# MAX30003.net
KiCad netlist of a schematic drawn in EAGLE
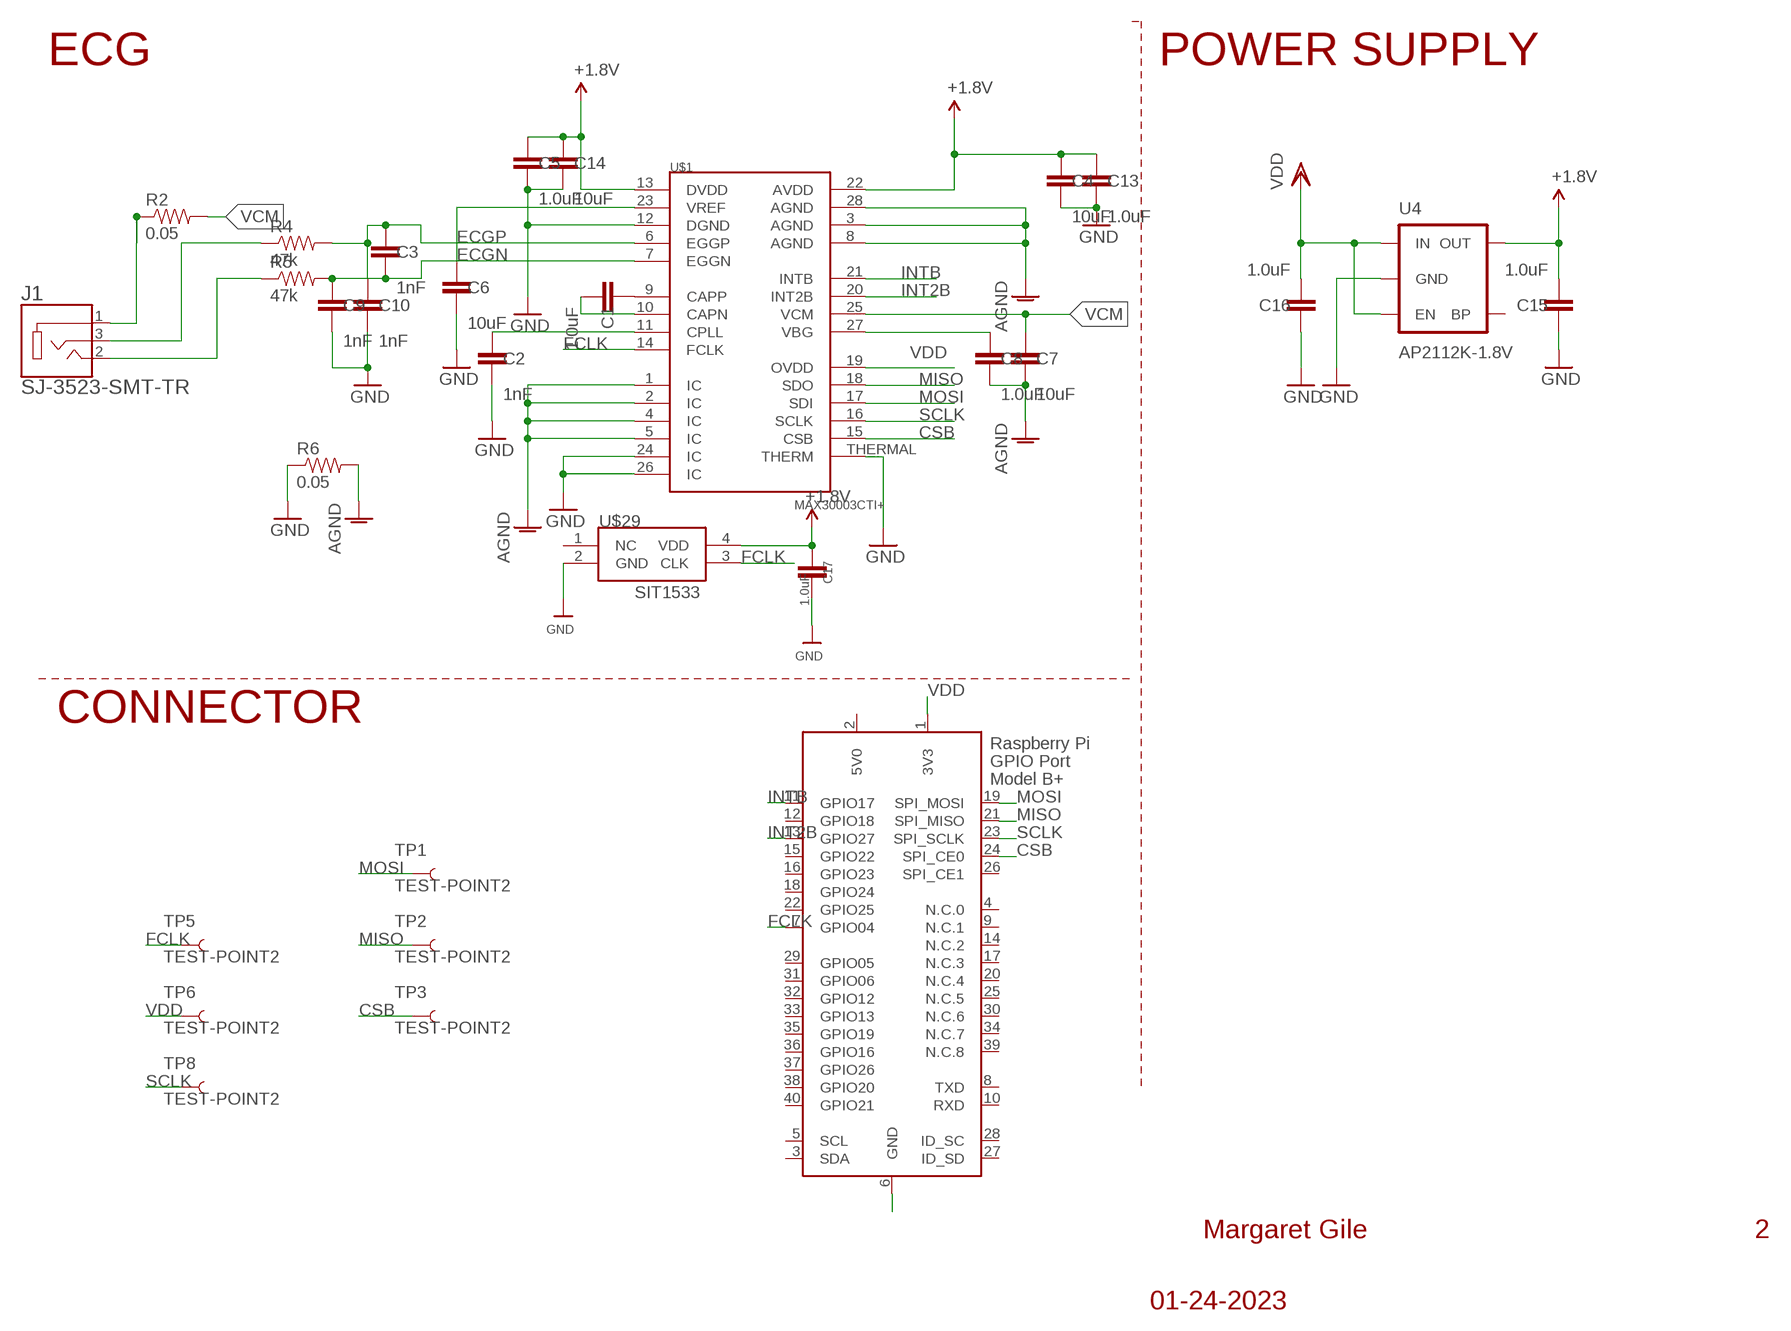
[diagram p0: schematic, sheet 1]

(export (version "E")
  (design (tool "Eeschema 10.0.6"))
  (components
    (comp (ref "C1")
      (value "1.0uF")
      (footprint "eagle-import:0603")
      (libsource (lib "eagle-import") (part "1.0UF-0603-16V-10%"))
    )
    (comp (ref "C2")
      (value "1nF")
      (footprint "eagle-import:0603")
      (libsource (lib "eagle-import") (part "1.0NF/1000PF-0603-50V-10%"))
    )
    (comp (ref "C3")
      (value "1nF")
      (footprint "eagle-import:0603")
      (libsource (lib "eagle-import") (part "1.0NF/1000PF-0603-50V-10%"))
    )
    (comp (ref "C4")
      (value "10uF")
      (footprint "eagle-import:0603")
      (libsource (lib "eagle-import") (part "10UF-0603-6.3V-20%"))
    )
    (comp (ref "C5")
      (value "1.0uF")
      (footprint "eagle-import:0603")
      (libsource (lib "eagle-import") (part "1.0UF-0603-16V-10%"))
    )
    (comp (ref "C6")
      (value "10uF")
      (footprint "eagle-import:0603")
      (libsource (lib "eagle-import") (part "10UF-0603-6.3V-20%"))
    )
    (comp (ref "C7")
      (value "10uF")
      (footprint "eagle-import:0603")
      (libsource (lib "eagle-import") (part "10UF-0603-6.3V-20%"))
    )
    (comp (ref "C8")
      (value "1.0uF")
      (footprint "eagle-import:0603")
      (libsource (lib "eagle-import") (part "1.0UF-0603-16V-10%"))
    )
    (comp (ref "C9")
      (value "1nF")
      (footprint "eagle-import:0603")
      (libsource (lib "eagle-import") (part "1.0NF/1000PF-0603-50V-10%"))
    )
    (comp (ref "C10")
      (value "1nF")
      (footprint "eagle-import:0603")
      (libsource (lib "eagle-import") (part "1.0NF/1000PF-0603-50V-10%"))
    )
    (comp (ref "C13")
      (value "1.0uF")
      (footprint "eagle-import:0603")
      (libsource (lib "eagle-import") (part "1.0UF-0603-16V-10%"))
    )
    (comp (ref "C14")
      (value "10uF")
      (footprint "eagle-import:0603")
      (libsource (lib "eagle-import") (part "10UF-0603-6.3V-20%"))
    )
    (comp (ref "C15")
      (value "1.0uF")
      (footprint "eagle-import:0603")
      (libsource (lib "eagle-import") (part "1.0UF-0603-16V-10%"))
    )
    (comp (ref "C16")
      (value "1.0uF")
      (footprint "eagle-import:0603")
      (libsource (lib "eagle-import") (part "1.0UF-0603-16V-10%"))
    )
    (comp (ref "C17")
      (value "1.0uF")
      (footprint "eagle-import:0603")
      (libsource (lib "eagle-import") (part "1.0UF-0603-16V-10%"))
    )
    (comp (ref "J1")
      (value "SJ-3523-SMT-TR")
      (footprint "eagle-import:CUI_SJ-3523-SMT-TR")
      (fields (field (name "MF") "CUI Devices"))
      (libsource (lib "eagle-import") (part "SJ-3523-SMT-TR"))
    )
    (comp (ref "R2")
      (value "0.05")
      (footprint "eagle-import:0603")
      (libsource (lib "eagle-import") (part "0.05OHM-0603-1/5W-1%"))
    )
    (comp (ref "R4")
      (value "47k")
      (footprint "eagle-import:0603")
      (libsource (lib "eagle-import") (part "47KOHM-0603-1/10W-1%"))
    )
    (comp (ref "R5")
      (value "47k")
      (footprint "eagle-import:0603")
      (libsource (lib "eagle-import") (part "47KOHM-0603-1/10W-1%"))
    )
    (comp (ref "R6")
      (value "0.05")
      (footprint "eagle-import:0603")
      (libsource (lib "eagle-import") (part "0.05OHM-0603-1/5W-1%"))
    )
    (comp (ref "TP1")
      (value "TEST-POINT2")
      (footprint "eagle-import:PAD.02X.02")
      (libsource (lib "eagle-import") (part "TEST-POINT2"))
    )
    (comp (ref "TP2")
      (value "TEST-POINT2")
      (footprint "eagle-import:PAD.02X.02")
      (libsource (lib "eagle-import") (part "TEST-POINT2"))
    )
    (comp (ref "TP3")
      (value "TEST-POINT2")
      (footprint "eagle-import:PAD.02X.02")
      (libsource (lib "eagle-import") (part "TEST-POINT2"))
    )
    (comp (ref "TP5")
      (value "TEST-POINT2")
      (footprint "eagle-import:PAD.02X.02")
      (libsource (lib "eagle-import") (part "TEST-POINT2"))
    )
    (comp (ref "TP6")
      (value "TEST-POINT2")
      (footprint "eagle-import:PAD.02X.02")
      (libsource (lib "eagle-import") (part "TEST-POINT2"))
    )
    (comp (ref "TP8")
      (value "TEST-POINT2")
      (footprint "eagle-import:PAD.02X.02")
      (libsource (lib "eagle-import") (part "TEST-POINT2"))
    )
    (comp (ref "U$1")
      (value "MAX30003CTI+")
      (footprint "eagle-import:QFN-28")
      (libsource (lib "eagle-import") (part "MAX30003"))
    )
    (comp (ref "U$29")
      (value "SIT1533")
      (footprint "eagle-import:SIT1533")
      (libsource (lib "eagle-import") (part "SIT1533"))
    )
    (comp (ref "U4")
      (value "AP2112K-1.8V")
      (footprint "eagle-import:SOT23-5")
      (libsource (lib "eagle-import") (part "V_REG_LDOSMD"))
    )
    (comp (ref "X1")
      (value "RASPI_BOARD_B+_HDC")
      (footprint "eagle-import:RASPI_BOARD_B+HAT_DF_CF")
      (libsource (lib "eagle-import") (part "RASPI_BOARD_B+_HDC"))
    )
  )
  (nets
    (net (code "1") (name "+1.8V") (class "Default")
      (node (ref "C13") (pin "1") (pinfunction "1_1") (pintype "passive"))
      (node (ref "C14") (pin "1") (pinfunction "1_1") (pintype "passive"))
      (node (ref "C15") (pin "2") (pinfunction "2_2") (pintype "passive"))
      (node (ref "C17") (pin "1") (pinfunction "1_1") (pintype "passive"))
      (node (ref "C4") (pin "1") (pinfunction "1_1") (pintype "passive"))
      (node (ref "C5") (pin "1") (pinfunction "1_1") (pintype "passive"))
      (node (ref "U$1") (pin "13") (pinfunction "DVDD_13") (pintype "bidirectional"))
      (node (ref "U$1") (pin "22") (pinfunction "AVDD_22") (pintype "bidirectional"))
      (node (ref "U$29") (pin "4") (pinfunction "VDD_4") (pintype "bidirectional"))
      (node (ref "U4") (pin "5") (pinfunction "OUT_5") (pintype "passive"))
    )
    (net (code "2") (name "/5V0") (class "Default")
      (node (ref "X1") (pin "2") (pinfunction "5V0_2") (pintype "power_in"))
    )
    (net (code "3") (name "/CSB") (class "Default")
      (node (ref "TP3") (pin "P$1") (pinfunction "1_P$1") (pintype "bidirectional"))
      (node (ref "U$1") (pin "15") (pinfunction "CSB_15") (pintype "bidirectional"))
      (node (ref "X1") (pin "24") (pinfunction "SPI_CE0_24") (pintype "bidirectional"))
    )
    (net (code "4") (name "/ECGN") (class "Default")
      (node (ref "C3") (pin "2") (pinfunction "2_2") (pintype "passive"))
      (node (ref "C9") (pin "1") (pinfunction "1_1") (pintype "passive"))
      (node (ref "R5") (pin "2") (pinfunction "2_2") (pintype "passive"))
      (node (ref "U$1") (pin "7") (pinfunction "EGGN_7") (pintype "bidirectional"))
    )
    (net (code "5") (name "/ECGP") (class "Default")
      (node (ref "C10") (pin "1") (pinfunction "1_1") (pintype "passive"))
      (node (ref "C3") (pin "1") (pinfunction "1_1") (pintype "passive"))
      (node (ref "R4") (pin "2") (pinfunction "2_2") (pintype "passive"))
      (node (ref "U$1") (pin "6") (pinfunction "EGGP_6") (pintype "bidirectional"))
    )
    (net (code "6") (name "/FCLK") (class "Default")
      (node (ref "TP5") (pin "P$1") (pinfunction "1_P$1") (pintype "bidirectional"))
      (node (ref "U$1") (pin "14") (pinfunction "FCLK_14") (pintype "bidirectional"))
      (node (ref "U$29") (pin "3") (pinfunction "CLK_3") (pintype "bidirectional"))
      (node (ref "X1") (pin "7") (pinfunction "GPIO04_7") (pintype "bidirectional"))
    )
    (net (code "7") (name "/INT2B") (class "Default")
      (node (ref "U$1") (pin "20") (pinfunction "INT2B_20") (pintype "bidirectional"))
      (node (ref "X1") (pin "13") (pinfunction "GPIO27_13") (pintype "bidirectional"))
    )
    (net (code "8") (name "/INTB") (class "Default")
      (node (ref "U$1") (pin "21") (pinfunction "INTB_21") (pintype "bidirectional"))
      (node (ref "X1") (pin "11") (pinfunction "GPIO17_11") (pintype "bidirectional"))
    )
    (net (code "9") (name "/MISO") (class "Default")
      (node (ref "TP2") (pin "P$1") (pinfunction "1_P$1") (pintype "bidirectional"))
      (node (ref "U$1") (pin "18") (pinfunction "SDO_18") (pintype "bidirectional"))
      (node (ref "X1") (pin "21") (pinfunction "SPI_MISO_21") (pintype "bidirectional"))
    )
    (net (code "10") (name "/MOSI") (class "Default")
      (node (ref "TP1") (pin "P$1") (pinfunction "1_P$1") (pintype "bidirectional"))
      (node (ref "U$1") (pin "17") (pinfunction "SDI_17") (pintype "bidirectional"))
      (node (ref "X1") (pin "19") (pinfunction "SPI_MOSI_19") (pintype "bidirectional"))
    )
    (net (code "11") (name "/SCLK") (class "Default")
      (node (ref "TP8") (pin "P$1") (pinfunction "1_P$1") (pintype "bidirectional"))
      (node (ref "U$1") (pin "16") (pinfunction "SCLK_16") (pintype "bidirectional"))
      (node (ref "X1") (pin "23") (pinfunction "SPI_SCLK_23") (pintype "bidirectional"))
    )
    (net (code "12") (name "AGND") (class "Default")
      (node (ref "C7") (pin "2") (pinfunction "2_2") (pintype "passive"))
      (node (ref "C8") (pin "2") (pinfunction "2_2") (pintype "passive"))
      (node (ref "R6") (pin "2") (pinfunction "2_2") (pintype "passive"))
      (node (ref "U$1") (pin "1") (pinfunction "IC_1") (pintype "bidirectional"))
      (node (ref "U$1") (pin "2") (pinfunction "IC_2") (pintype "bidirectional"))
      (node (ref "U$1") (pin "28") (pinfunction "AGND_28") (pintype "bidirectional"))
      (node (ref "U$1") (pin "3") (pinfunction "AGND_3") (pintype "bidirectional"))
      (node (ref "U$1") (pin "4") (pinfunction "IC_4") (pintype "bidirectional"))
      (node (ref "U$1") (pin "5") (pinfunction "IC_5") (pintype "bidirectional"))
      (node (ref "U$1") (pin "8") (pinfunction "AGND_8") (pintype "bidirectional"))
    )
    (net (code "13") (name "GND") (class "Default")
      (node (ref "C10") (pin "2") (pinfunction "2_2") (pintype "passive"))
      (node (ref "C13") (pin "2") (pinfunction "2_2") (pintype "passive"))
      (node (ref "C14") (pin "2") (pinfunction "2_2") (pintype "passive"))
      (node (ref "C15") (pin "1") (pinfunction "1_1") (pintype "passive"))
      (node (ref "C16") (pin "1") (pinfunction "1_1") (pintype "passive"))
      (node (ref "C17") (pin "2") (pinfunction "2_2") (pintype "passive"))
      (node (ref "C2") (pin "2") (pinfunction "2_2") (pintype "passive"))
      (node (ref "C4") (pin "2") (pinfunction "2_2") (pintype "passive"))
      (node (ref "C5") (pin "2") (pinfunction "2_2") (pintype "passive"))
      (node (ref "C6") (pin "2") (pinfunction "2_2") (pintype "passive"))
      (node (ref "C9") (pin "2") (pinfunction "2_2") (pintype "passive"))
      (node (ref "R6") (pin "1") (pinfunction "1_1") (pintype "passive"))
      (node (ref "U$1") (pin "12") (pinfunction "DGND_12") (pintype "bidirectional"))
      (node (ref "U$1") (pin "24") (pinfunction "IC_24") (pintype "bidirectional"))
      (node (ref "U$1") (pin "26") (pinfunction "IC_26") (pintype "bidirectional"))
      (node (ref "U$1") (pin "THERMAL") (pinfunction "THERM_THERMAL") (pintype "bidirectional"))
      (node (ref "U$29") (pin "2") (pinfunction "GND_2") (pintype "bidirectional"))
      (node (ref "U4") (pin "2") (pinfunction "GND_2") (pintype "input"))
    )
    (net (code "14") (name "Net-(J1-Pad1)") (class "Default")
      (node (ref "J1") (pin "1") (pinfunction "1_1") (pintype "passive"))
      (node (ref "R2") (pin "1") (pinfunction "1_1") (pintype "passive"))
    )
    (net (code "15") (name "Net-(J1-Pad2)") (class "Default")
      (node (ref "J1") (pin "2") (pinfunction "2_2") (pintype "passive"))
      (node (ref "R5") (pin "1") (pinfunction "1_1") (pintype "passive"))
    )
    (net (code "16") (name "Net-(J1-Pad3)") (class "Default")
      (node (ref "J1") (pin "3") (pinfunction "3_3") (pintype "passive"))
      (node (ref "R4") (pin "1") (pinfunction "1_1") (pintype "passive"))
    )
    (net (code "17") (name "Net-(U$1-CAPN)") (class "Default")
      (node (ref "C1") (pin "2") (pinfunction "2_2") (pintype "passive"))
      (node (ref "U$1") (pin "10") (pinfunction "CAPN_10") (pintype "bidirectional"))
    )
    (net (code "18") (name "Net-(U$1-CAPP)") (class "Default")
      (node (ref "C1") (pin "1") (pinfunction "1_1") (pintype "passive"))
      (node (ref "U$1") (pin "9") (pinfunction "CAPP_9") (pintype "bidirectional"))
    )
    (net (code "19") (name "Net-(U$1-CPLL)") (class "Default")
      (node (ref "C2") (pin "1") (pinfunction "1_1") (pintype "passive"))
      (node (ref "U$1") (pin "11") (pinfunction "CPLL_11") (pintype "bidirectional"))
    )
    (net (code "20") (name "Net-(U$1-VBG)") (class "Default")
      (node (ref "C8") (pin "1") (pinfunction "1_1") (pintype "passive"))
      (node (ref "U$1") (pin "27") (pinfunction "VBG_27") (pintype "bidirectional"))
    )
    (net (code "21") (name "Net-(U$1-VREF)") (class "Default")
      (node (ref "C6") (pin "1") (pinfunction "1_1") (pintype "passive"))
      (node (ref "U$1") (pin "23") (pinfunction "VREF_23") (pintype "bidirectional"))
    )
    (net (code "22") (name "VCM") (class "Default")
      (node (ref "C7") (pin "1") (pinfunction "1_1") (pintype "passive"))
      (node (ref "R2") (pin "2") (pinfunction "2_2") (pintype "passive"))
      (node (ref "U$1") (pin "25") (pinfunction "VCM_25") (pintype "bidirectional"))
    )
    (net (code "23") (name "VDD") (class "Default")
      (node (ref "C16") (pin "2") (pinfunction "2_2") (pintype "passive"))
      (node (ref "TP6") (pin "P$1") (pinfunction "1_P$1") (pintype "bidirectional"))
      (node (ref "U$1") (pin "19") (pinfunction "OVDD_19") (pintype "bidirectional"))
      (node (ref "U4") (pin "1") (pinfunction "IN_1") (pintype "input"))
      (node (ref "U4") (pin "3") (pinfunction "EN_3") (pintype "input"))
      (node (ref "X1") (pin "1") (pinfunction "3V3_1") (pintype "power_in"))
    )
    (net (code "24") (name "unconnected-(U$29-NC-Pad1)") (class "Default")
      (node (ref "U$29") (pin "1") (pinfunction "NC_1") (pintype "bidirectional"))
    )
    (net (code "25") (name "unconnected-(U4-BP-Pad4)") (class "Default")
      (node (ref "U4") (pin "4") (pinfunction "BP_4") (pintype "input"))
    )
    (net (code "26") (name "unconnected-(X1-GND-Pad6)") (class "Default")
      (node (ref "X1") (pin "6") (pinfunction "GND_6") (pintype "power_in"))
    )
    (net (code "27") (name "unconnected-(X1-GPIO05-Pad29)") (class "Default")
      (node (ref "X1") (pin "29") (pinfunction "GPIO05_29") (pintype "no_connect"))
    )
    (net (code "28") (name "unconnected-(X1-GPIO06-Pad31)") (class "Default")
      (node (ref "X1") (pin "31") (pinfunction "GPIO06_31") (pintype "no_connect"))
    )
    (net (code "29") (name "unconnected-(X1-GPIO12-Pad32)") (class "Default")
      (node (ref "X1") (pin "32") (pinfunction "GPIO12_32") (pintype "no_connect"))
    )
    (net (code "30") (name "unconnected-(X1-GPIO13-Pad33)") (class "Default")
      (node (ref "X1") (pin "33") (pinfunction "GPIO13_33") (pintype "no_connect"))
    )
    (net (code "31") (name "unconnected-(X1-GPIO16-Pad36)") (class "Default")
      (node (ref "X1") (pin "36") (pinfunction "GPIO16_36") (pintype "no_connect"))
    )
    (net (code "32") (name "unconnected-(X1-GPIO18-Pad12)") (class "Default")
      (node (ref "X1") (pin "12") (pinfunction "GPIO18_12") (pintype "bidirectional"))
    )
    (net (code "33") (name "unconnected-(X1-GPIO19-Pad35)") (class "Default")
      (node (ref "X1") (pin "35") (pinfunction "GPIO19_35") (pintype "no_connect"))
    )
    (net (code "34") (name "unconnected-(X1-GPIO20-Pad38)") (class "Default")
      (node (ref "X1") (pin "38") (pinfunction "GPIO20_38") (pintype "no_connect"))
    )
    (net (code "35") (name "unconnected-(X1-GPIO21-Pad40)") (class "Default")
      (node (ref "X1") (pin "40") (pinfunction "GPIO21_40") (pintype "no_connect"))
    )
    (net (code "36") (name "unconnected-(X1-GPIO22-Pad15)") (class "Default")
      (node (ref "X1") (pin "15") (pinfunction "GPIO22_15") (pintype "bidirectional"))
    )
    (net (code "37") (name "unconnected-(X1-GPIO23-Pad16)") (class "Default")
      (node (ref "X1") (pin "16") (pinfunction "GPIO23_16") (pintype "bidirectional"))
    )
    (net (code "38") (name "unconnected-(X1-GPIO24-Pad18)") (class "Default")
      (node (ref "X1") (pin "18") (pinfunction "GPIO24_18") (pintype "bidirectional"))
    )
    (net (code "39") (name "unconnected-(X1-GPIO25-Pad22)") (class "Default")
      (node (ref "X1") (pin "22") (pinfunction "GPIO25_22") (pintype "bidirectional"))
    )
    (net (code "40") (name "unconnected-(X1-GPIO26-Pad37)") (class "Default")
      (node (ref "X1") (pin "37") (pinfunction "GPIO26_37") (pintype "no_connect"))
    )
    (net (code "41") (name "unconnected-(X1-ID_SC-Pad28)") (class "Default")
      (node (ref "X1") (pin "28") (pinfunction "ID_SC_28") (pintype "no_connect"))
    )
    (net (code "42") (name "unconnected-(X1-ID_SD-Pad27)") (class "Default")
      (node (ref "X1") (pin "27") (pinfunction "ID_SD_27") (pintype "no_connect"))
    )
    (net (code "43") (name "unconnected-(X1-N.C.0-Pad4)") (class "Default")
      (node (ref "X1") (pin "4") (pinfunction "N.C.0_4") (pintype "no_connect"))
    )
    (net (code "44") (name "unconnected-(X1-N.C.1-Pad9)") (class "Default")
      (node (ref "X1") (pin "9") (pinfunction "N.C.1_9") (pintype "no_connect"))
    )
    (net (code "45") (name "unconnected-(X1-N.C.2-Pad14)") (class "Default")
      (node (ref "X1") (pin "14") (pinfunction "N.C.2_14") (pintype "no_connect"))
    )
    (net (code "46") (name "unconnected-(X1-N.C.3-Pad17)") (class "Default")
      (node (ref "X1") (pin "17") (pinfunction "N.C.3_17") (pintype "no_connect"))
    )
    (net (code "47") (name "unconnected-(X1-N.C.4-Pad20)") (class "Default")
      (node (ref "X1") (pin "20") (pinfunction "N.C.4_20") (pintype "no_connect"))
    )
    (net (code "48") (name "unconnected-(X1-N.C.5-Pad25)") (class "Default")
      (node (ref "X1") (pin "25") (pinfunction "N.C.5_25") (pintype "no_connect"))
    )
    (net (code "49") (name "unconnected-(X1-N.C.6-Pad30)") (class "Default")
      (node (ref "X1") (pin "30") (pinfunction "N.C.6_30") (pintype "no_connect"))
    )
    (net (code "50") (name "unconnected-(X1-N.C.7-Pad34)") (class "Default")
      (node (ref "X1") (pin "34") (pinfunction "N.C.7_34") (pintype "no_connect"))
    )
    (net (code "51") (name "unconnected-(X1-N.C.8-Pad39)") (class "Default")
      (node (ref "X1") (pin "39") (pinfunction "N.C.8_39") (pintype "no_connect"))
    )
    (net (code "52") (name "unconnected-(X1-RXD-Pad10)") (class "Default")
      (node (ref "X1") (pin "10") (pinfunction "RXD_10") (pintype "bidirectional"))
    )
    (net (code "53") (name "unconnected-(X1-SCL-Pad5)") (class "Default")
      (node (ref "X1") (pin "5") (pinfunction "SCL_5") (pintype "bidirectional"))
    )
    (net (code "54") (name "unconnected-(X1-SDA-Pad3)") (class "Default")
      (node (ref "X1") (pin "3") (pinfunction "SDA_3") (pintype "bidirectional"))
    )
    (net (code "55") (name "unconnected-(X1-SPI_CE1-Pad26)") (class "Default")
      (node (ref "X1") (pin "26") (pinfunction "SPI_CE1_26") (pintype "bidirectional"))
    )
    (net (code "56") (name "unconnected-(X1-TXD-Pad8)") (class "Default")
      (node (ref "X1") (pin "8") (pinfunction "TXD_8") (pintype "bidirectional"))
    )
  )
)
